# SmartController.net
KiCad netlist of a schematic drawn in EAGLE
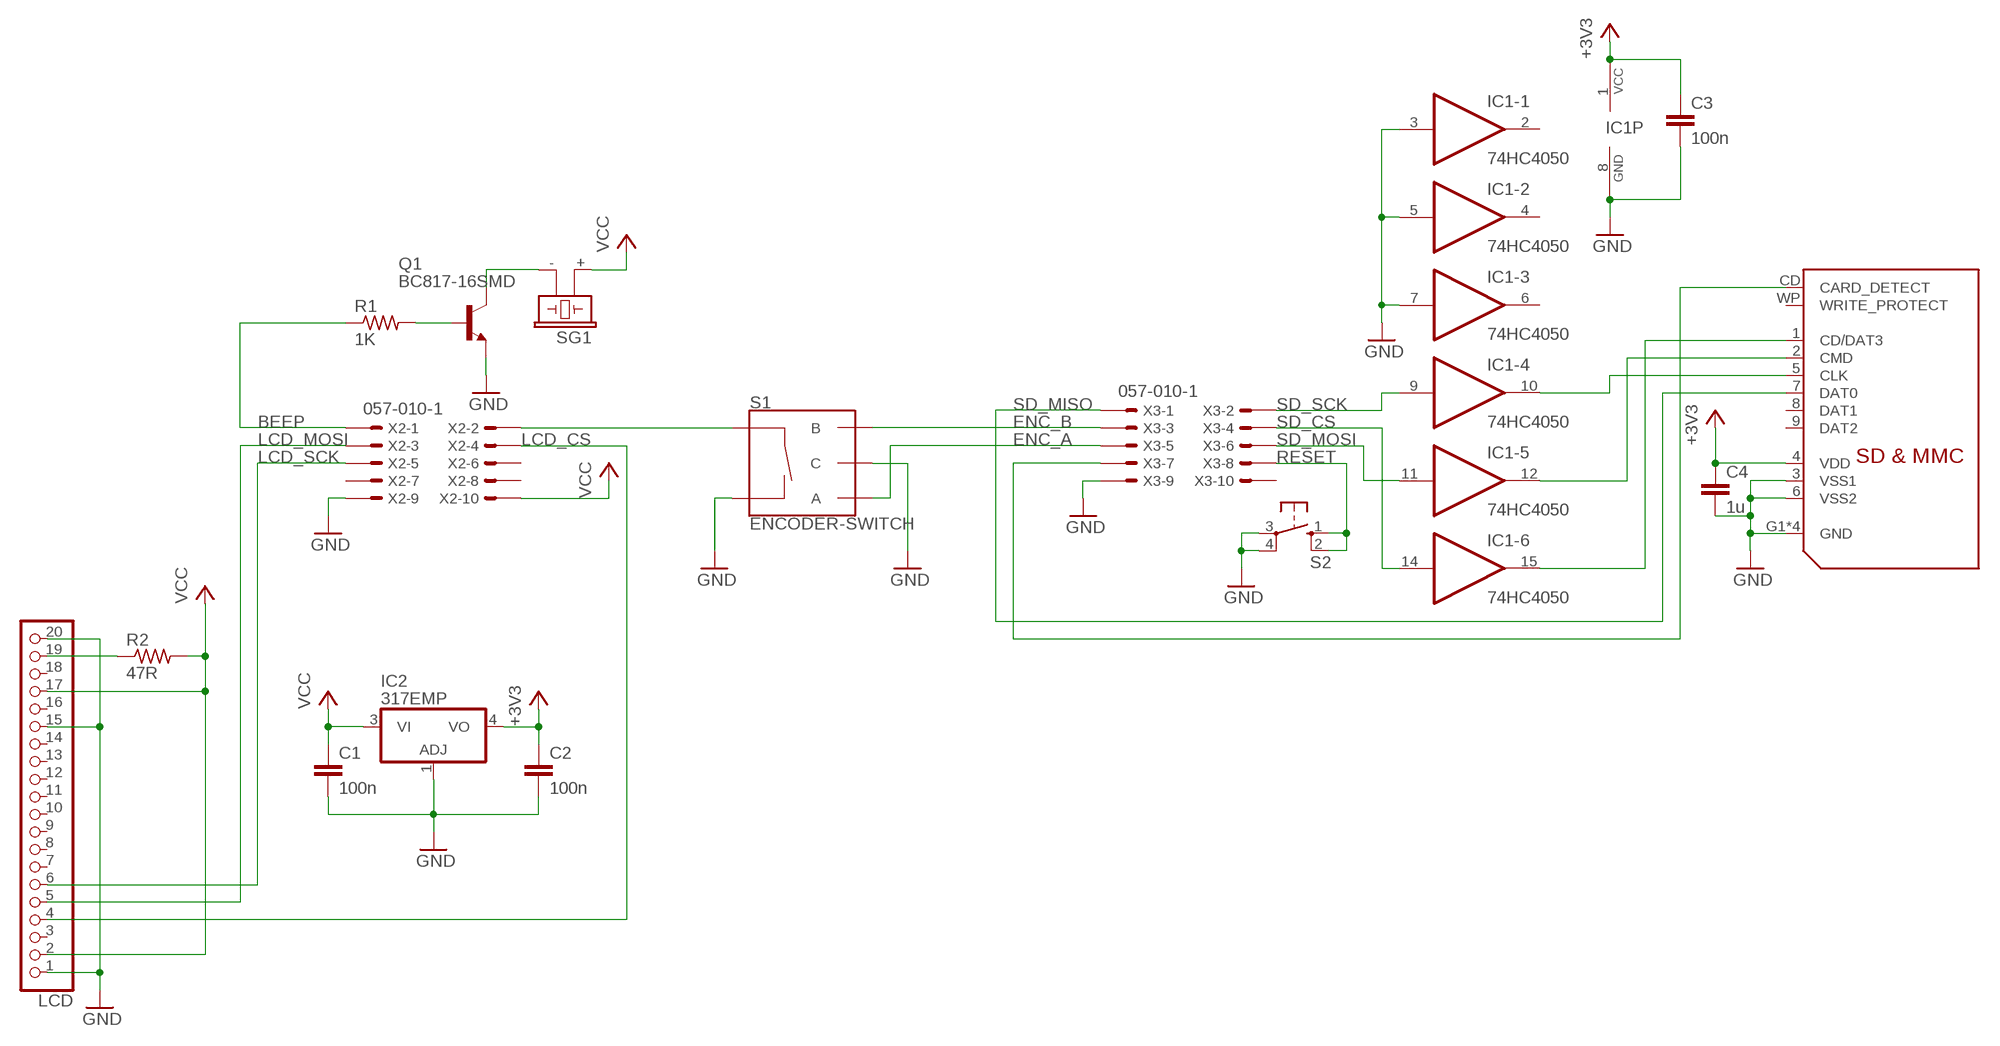
[diagram p0: schematic, sheet 1]

(export (version "E")
  (design (tool "Eeschema 10.0.6"))
  (components
    (comp (ref "C1")
      (value "100n")
      (footprint "eagle-import:C0805")
      (libsource (lib "eagle-import") (part "C-EUC0805"))
    )
    (comp (ref "C2")
      (value "100n")
      (footprint "eagle-import:C0805")
      (libsource (lib "eagle-import") (part "C-EUC0805"))
    )
    (comp (ref "C3")
      (value "100n")
      (footprint "eagle-import:C0805")
      (libsource (lib "eagle-import") (part "C-EUC0805"))
    )
    (comp (ref "C4")
      (value "1u")
      (footprint "eagle-import:C0805")
      (libsource (lib "eagle-import") (part "C-EUC0805"))
    )
    (comp (ref "IC1")
      (value "74HC4050")
      (footprint "eagle-import:SO16")
      (libsource (lib "eagle-import") (part "74HC4050"))
    )
    (comp (ref "IC2")
      (value "317EMP")
      (footprint "eagle-import:SOT223")
      (libsource (lib "eagle-import") (part "317EMP"))
    )
    (comp (ref "LCD")
      (value "PINHD-1X20")
      (footprint "eagle-import:1X20")
      (libsource (lib "eagle-import") (part "PINHD-1X20"))
    )
    (comp (ref "Q1")
      (value "BC817-16SMD")
      (footprint "eagle-import:SOT23-BEC")
      (libsource (lib "eagle-import") (part "BC817SMD-16"))
    )
    (comp (ref "R1")
      (value "1K")
      (footprint "eagle-import:R0805")
      (libsource (lib "eagle-import") (part "R-US_R0805"))
    )
    (comp (ref "R2")
      (value "47R")
      (footprint "eagle-import:R0805")
      (libsource (lib "eagle-import") (part "R-US_R0805"))
    )
    (comp (ref "S1")
      (value "ENCODER-SWITCH")
      (footprint "eagle-import:ROTARY_ENC_PLAIN")
      (libsource (lib "eagle-import") (part "ENCODER-SWITCH"))
    )
    (comp (ref "S2")
      (value "10-XX")
      (footprint "eagle-import:B3F-10XX")
      (fields (field (name "MPN") "B3F-1000"))
      (libsource (lib "eagle-import") (part "10-XX"))
    )
    (comp (ref "SG1")
      (value "F/CM12P")
      (footprint "eagle-import:F_CM12P")
      (libsource (lib "eagle-import") (part "F/CM12P"))
    )
    (comp (ref "X1")
      (value "TE-2041021")
      (footprint "eagle-import:2041021")
      (libsource (lib "eagle-import") (part "TE-2041021"))
    )
    (comp (ref "X2")
      (value "057-010-1")
      (footprint "eagle-import:057-010-1")
      (libsource (lib "eagle-import") (part "057-010-1"))
    )
    (comp (ref "X3")
      (value "057-010-1")
      (footprint "eagle-import:057-010-1")
      (libsource (lib "eagle-import") (part "057-010-1"))
    )
  )
  (nets
    (net (code "1") (name "+3V3") (class "Default")
      (node (ref "C2") (pin "1") (pinfunction "1_1") (pintype "passive"))
      (node (ref "C3") (pin "1") (pinfunction "1_1") (pintype "passive"))
      (node (ref "C4") (pin "1") (pinfunction "1_1") (pintype "passive"))
      (node (ref "IC1") (pin "1") (pinfunction "VCC_1") (pintype "power_in"))
      (node (ref "IC2") (pin "4") (pinfunction "VO_4") (pintype "passive"))
      (node (ref "X1") (pin "4") (pinfunction "VDD_4") (pintype "power_in"))
    )
    (net (code "2") (name "/BEEP") (class "Default")
      (node (ref "R1") (pin "1") (pinfunction "1_1") (pintype "passive"))
      (node (ref "X2") (pin "1") (pinfunction "S_1") (pintype "passive"))
    )
    (net (code "3") (name "/ENC_A") (class "Default")
      (node (ref "S1") (pin "A") (pinfunction "A_A") (pintype "bidirectional"))
      (node (ref "X3") (pin "5") (pinfunction "S_5") (pintype "passive"))
    )
    (net (code "4") (name "/ENC_B") (class "Default")
      (node (ref "S1") (pin "B") (pinfunction "B_B") (pintype "bidirectional"))
      (node (ref "X3") (pin "3") (pinfunction "S_3") (pintype "passive"))
    )
    (net (code "5") (name "/LCD_CS") (class "Default")
      (node (ref "LCD") (pin "4") (pinfunction "4_4") (pintype "passive"))
      (node (ref "X2") (pin "4") (pinfunction "S_4") (pintype "passive"))
    )
    (net (code "6") (name "/LCD_MOSI") (class "Default")
      (node (ref "LCD") (pin "5") (pinfunction "5_5") (pintype "passive"))
      (node (ref "X2") (pin "3") (pinfunction "S_3") (pintype "passive"))
    )
    (net (code "7") (name "/LCD_SCK") (class "Default")
      (node (ref "LCD") (pin "6") (pinfunction "6_6") (pintype "passive"))
      (node (ref "X2") (pin "5") (pinfunction "S_5") (pintype "passive"))
    )
    (net (code "8") (name "/RESET") (class "Default")
      (node (ref "S2") (pin "1") (pinfunction "S_1") (pintype "passive"))
      (node (ref "S2") (pin "2") (pinfunction "S1_2") (pintype "passive"))
      (node (ref "X3") (pin "8") (pinfunction "S_8") (pintype "passive"))
    )
    (net (code "9") (name "/SD_CS") (class "Default")
      (node (ref "IC1") (pin "14") (pinfunction "I_14") (pintype "input"))
      (node (ref "X3") (pin "4") (pinfunction "S_4") (pintype "passive"))
    )
    (net (code "10") (name "/SD_MISO") (class "Default")
      (node (ref "X1") (pin "7") (pinfunction "DAT0_7") (pintype "input"))
      (node (ref "X3") (pin "1") (pinfunction "S_1") (pintype "passive"))
    )
    (net (code "11") (name "/SD_MOSI") (class "Default")
      (node (ref "IC1") (pin "11") (pinfunction "I_11") (pintype "input"))
      (node (ref "X3") (pin "6") (pinfunction "S_6") (pintype "passive"))
    )
    (net (code "12") (name "/SD_SCK") (class "Default")
      (node (ref "IC1") (pin "9") (pinfunction "I_9") (pintype "input"))
      (node (ref "X3") (pin "2") (pinfunction "S_2") (pintype "passive"))
    )
    (net (code "13") (name "GND") (class "Default")
      (node (ref "C1") (pin "2") (pinfunction "2_2") (pintype "passive"))
      (node (ref "C2") (pin "2") (pinfunction "2_2") (pintype "passive"))
      (node (ref "C3") (pin "2") (pinfunction "2_2") (pintype "passive"))
      (node (ref "C4") (pin "2") (pinfunction "2_2") (pintype "passive"))
      (node (ref "IC1") (pin "3") (pinfunction "I_3") (pintype "input"))
      (node (ref "IC1") (pin "5") (pinfunction "I_5") (pintype "input"))
      (node (ref "IC1") (pin "7") (pinfunction "I_7") (pintype "input"))
      (node (ref "IC1") (pin "8") (pinfunction "GND_8") (pintype "power_in"))
      (node (ref "IC2") (pin "1") (pinfunction "ADJ_1") (pintype "input"))
      (node (ref "LCD") (pin "1") (pinfunction "1_1") (pintype "passive"))
      (node (ref "LCD") (pin "15") (pinfunction "15_15") (pintype "passive"))
      (node (ref "LCD") (pin "20") (pinfunction "20_20") (pintype "passive"))
      (node (ref "Q1") (pin "E") (pinfunction "E_E") (pintype "passive"))
      (node (ref "S1") (pin "C") (pinfunction "C_C") (pintype "bidirectional"))
      (node (ref "S1") (pin "SW-") (pinfunction "SW-_SW-") (pintype "bidirectional"))
      (node (ref "S2") (pin "3") (pinfunction "P_3") (pintype "passive"))
      (node (ref "S2") (pin "4") (pinfunction "P1_4") (pintype "passive"))
      (node (ref "X1") (pin "3") (pinfunction "VSS1_3") (pintype "power_in"))
      (node (ref "X1") (pin "6") (pinfunction "VSS2_6") (pintype "power_in"))
      (node (ref "X1") (pin "G1") (pinfunction "GND_G1") (pintype "power_in"))
      (node (ref "X1") (pin "G2") (pinfunction "GND_G2") (pintype "power_in"))
      (node (ref "X1") (pin "G3") (pinfunction "GND_G3") (pintype "power_in"))
      (node (ref "X1") (pin "G4") (pinfunction "GND_G4") (pintype "power_in"))
      (node (ref "X2") (pin "9") (pinfunction "S_9") (pintype "passive"))
      (node (ref "X3") (pin "9") (pinfunction "S_9") (pintype "passive"))
    )
    (net (code "14") (name "Net-(IC1D-O)") (class "Default")
      (node (ref "IC1") (pin "10") (pinfunction "O_10") (pintype "open_collector"))
      (node (ref "X1") (pin "5") (pinfunction "CLK_5") (pintype "input"))
    )
    (net (code "15") (name "Net-(IC1E-O)") (class "Default")
      (node (ref "IC1") (pin "12") (pinfunction "O_12") (pintype "open_collector"))
      (node (ref "X1") (pin "2") (pinfunction "CMD_2") (pintype "input"))
    )
    (net (code "16") (name "Net-(IC1F-O)") (class "Default")
      (node (ref "IC1") (pin "15") (pinfunction "O_15") (pintype "open_collector"))
      (node (ref "X1") (pin "1") (pinfunction "CD/DAT3_1") (pintype "output"))
    )
    (net (code "17") (name "Net-(LCD-Pad19)") (class "Default")
      (node (ref "LCD") (pin "19") (pinfunction "19_19") (pintype "passive"))
      (node (ref "R2") (pin "1") (pinfunction "1_1") (pintype "passive"))
    )
    (net (code "18") (name "Net-(Q1-PadB)") (class "Default")
      (node (ref "Q1") (pin "B") (pinfunction "B_B") (pintype "passive"))
      (node (ref "R1") (pin "2") (pinfunction "2_2") (pintype "passive"))
    )
    (net (code "19") (name "Net-(SG1-2)") (class "Default")
      (node (ref "Q1") (pin "C") (pinfunction "C_C") (pintype "passive"))
      (node (ref "SG1") (pin "-") (pinfunction "2_-") (pintype "passive"))
    )
    (net (code "20") (name "Net-(X1-CARD_DETECT)") (class "Default")
      (node (ref "X1") (pin "CD") (pinfunction "CARD_DETECT_CD") (pintype "passive"))
      (node (ref "X3") (pin "7") (pinfunction "S_7") (pintype "passive"))
    )
    (net (code "21") (name "Net-(X2C-S)") (class "Default")
      (node (ref "S1") (pin "SW+") (pinfunction "SW+_SW+") (pintype "bidirectional"))
      (node (ref "X2") (pin "2") (pinfunction "S_2") (pintype "passive"))
    )
    (net (code "22") (name "VCC") (class "Default")
      (node (ref "C1") (pin "1") (pinfunction "1_1") (pintype "passive"))
      (node (ref "IC2") (pin "3") (pinfunction "VI_3") (pintype "input"))
      (node (ref "LCD") (pin "17") (pinfunction "17_17") (pintype "passive"))
      (node (ref "LCD") (pin "2") (pinfunction "2_2") (pintype "passive"))
      (node (ref "R2") (pin "2") (pinfunction "2_2") (pintype "passive"))
      (node (ref "SG1") (pin "+") (pinfunction "1_+") (pintype "passive"))
      (node (ref "X2") (pin "10") (pinfunction "S_10") (pintype "passive"))
    )
    (net (code "23") (name "unconnected-(IC1A-O-Pad2)") (class "Default")
      (node (ref "IC1") (pin "2") (pinfunction "O_2") (pintype "open_collector"))
    )
    (net (code "24") (name "unconnected-(IC1B-O-Pad4)") (class "Default")
      (node (ref "IC1") (pin "4") (pinfunction "O_4") (pintype "open_collector"))
    )
    (net (code "25") (name "unconnected-(IC1C-O-Pad6)") (class "Default")
      (node (ref "IC1") (pin "6") (pinfunction "O_6") (pintype "open_collector"))
    )
    (net (code "26") (name "unconnected-(LCD-Pad3)") (class "Default")
      (node (ref "LCD") (pin "3") (pinfunction "3_3") (pintype "passive"))
    )
    (net (code "27") (name "unconnected-(LCD-Pad7)") (class "Default")
      (node (ref "LCD") (pin "7") (pinfunction "7_7") (pintype "passive"))
    )
    (net (code "28") (name "unconnected-(LCD-Pad8)") (class "Default")
      (node (ref "LCD") (pin "8") (pinfunction "8_8") (pintype "passive"))
    )
    (net (code "29") (name "unconnected-(LCD-Pad9)") (class "Default")
      (node (ref "LCD") (pin "9") (pinfunction "9_9") (pintype "passive"))
    )
    (net (code "30") (name "unconnected-(LCD-Pad10)") (class "Default")
      (node (ref "LCD") (pin "10") (pinfunction "10_10") (pintype "passive"))
    )
    (net (code "31") (name "unconnected-(LCD-Pad11)") (class "Default")
      (node (ref "LCD") (pin "11") (pinfunction "11_11") (pintype "passive"))
    )
    (net (code "32") (name "unconnected-(LCD-Pad12)") (class "Default")
      (node (ref "LCD") (pin "12") (pinfunction "12_12") (pintype "passive"))
    )
    (net (code "33") (name "unconnected-(LCD-Pad13)") (class "Default")
      (node (ref "LCD") (pin "13") (pinfunction "13_13") (pintype "passive"))
    )
    (net (code "34") (name "unconnected-(LCD-Pad14)") (class "Default")
      (node (ref "LCD") (pin "14") (pinfunction "14_14") (pintype "passive"))
    )
    (net (code "35") (name "unconnected-(LCD-Pad16)") (class "Default")
      (node (ref "LCD") (pin "16") (pinfunction "16_16") (pintype "passive"))
    )
    (net (code "36") (name "unconnected-(LCD-Pad18)") (class "Default")
      (node (ref "LCD") (pin "18") (pinfunction "18_18") (pintype "passive"))
    )
    (net (code "37") (name "unconnected-(X1-DAT1-Pad8)") (class "Default")
      (node (ref "X1") (pin "8") (pinfunction "DAT1_8") (pintype "bidirectional"))
    )
    (net (code "38") (name "unconnected-(X1-DAT2-Pad9)") (class "Default")
      (node (ref "X1") (pin "9") (pinfunction "DAT2_9") (pintype "bidirectional"))
    )
    (net (code "39") (name "unconnected-(X1-WRITE_PROTECT-PadWP)") (class "Default")
      (node (ref "X1") (pin "WP") (pinfunction "WRITE_PROTECT_WP") (pintype "passive"))
    )
    (net (code "40") (name "unconnected-(X2G-S-Pad6)") (class "Default")
      (node (ref "X2") (pin "6") (pinfunction "S_6") (pintype "passive"))
    )
    (net (code "41") (name "unconnected-(X2H-S-Pad7)") (class "Default")
      (node (ref "X2") (pin "7") (pinfunction "S_7") (pintype "passive"))
    )
    (net (code "42") (name "unconnected-(X2I-S-Pad8)") (class "Default")
      (node (ref "X2") (pin "8") (pinfunction "S_8") (pintype "passive"))
    )
    (net (code "43") (name "unconnected-(X3B-S-Pad10)") (class "Default")
      (node (ref "X3") (pin "10") (pinfunction "S_10") (pintype "passive"))
    )
  )
)
